# mic.net
KiCad netlist of a schematic drawn in Altium Designer
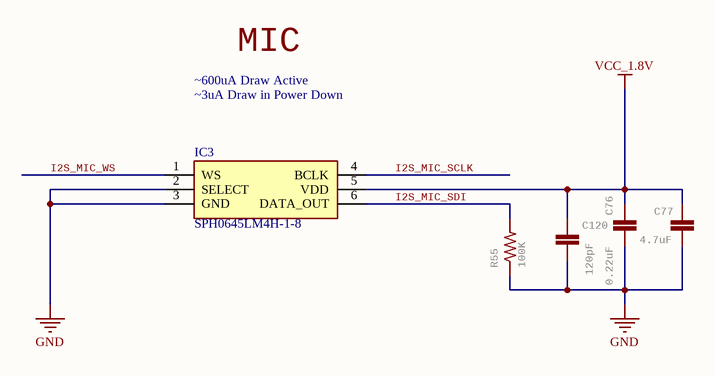
[diagram p0: mic.SchDoc]

(export (version "E")
  (design (tool "Eeschema 10.0.6"))
  (components
    (comp (ref "C76")
      (value "0.22uF")
      (footprint "C0201")
      (description "CAPACITOR, European symbol")
      (fields (field (name "MPN") "GRM033R60J224ME15D"))
      (libsource (lib "openmv-ae3") (part "C-EUC0201"))
    )
    (comp (ref "C77")
      (value "4.7uF")
      (footprint "0402-CAP")
      (description "CapacitorStandard 0603 ceramic capacitor, and 0.1\" leaded capacitor.")
      (fields (field (name "MPN") "JMK105BBJ475MV-F") (field (name "LIBRARYNAME") "sfe"))
      (libsource (lib "openmv-ae3") (part "CAP0402-CAP"))
    )
    (comp (ref "C120")
      (value "120pF")
      (footprint "C0201")
      (fields (field (name "MPN") "GRM033R71H121KA12D") (field (name "LIBRARYNAME") "sfe"))
      (libsource (lib "openmv-ae3") (part "CAP0402-CAP"))
    )
    (comp (ref "IC3")
      (value "SPH0645LM4H-1-8")
      (footprint "SamacSys:SPH0645LM4H18")
      (description "Integrated Circuit")
      (fields (field (name "MOUSER PART NUMBER") "721-SPH0645LM4H-1-8"))
      (libsource (lib "openmv-ae3") (part "SPH0645LM4H-1-8"))
    )
    (comp (ref "R55")
      (value "100K")
      (footprint "R0201")
      (fields (field (name "MPN") "RMCF0201FT100K") (field (name "LIBRARYNAME") "sfe"))
      (libsource (lib "openmv-ae3") (part "RESISTOR0402-RES"))
    )
  )
  (nets
    (net (code "1") (name "/I2S_MIC_SCLK") (class "Default")
      (node (ref "IC3") (pin "4") (pinfunction "BCLK_4") (pintype "passive"))
    )
    (net (code "2") (name "/I2S_MIC_SDI") (class "Default")
      (node (ref "IC3") (pin "6") (pinfunction "DATA_OUT_6") (pintype "passive"))
      (node (ref "R55") (pin "2") (pinfunction "2_2") (pintype "passive"))
    )
    (net (code "3") (name "/I2S_MIC_WS") (class "Default")
      (node (ref "IC3") (pin "1") (pinfunction "WS_1") (pintype "passive"))
    )
    (net (code "4") (name "GND") (class "Default")
      (node (ref "C120") (pin "1") (pinfunction "1_1") (pintype "passive"))
      (node (ref "C76") (pin "2") (pinfunction "2_2") (pintype "passive"))
      (node (ref "C77") (pin "1") (pinfunction "1_1") (pintype "passive"))
      (node (ref "IC3") (pin "2") (pinfunction "SELECT_2") (pintype "passive"))
      (node (ref "IC3") (pin "3") (pinfunction "GND_3") (pintype "passive"))
      (node (ref "R55") (pin "1") (pinfunction "1_1") (pintype "passive"))
    )
    (net (code "5") (name "VCC_1.8V") (class "Default")
      (node (ref "C120") (pin "2") (pinfunction "2_2") (pintype "passive"))
      (node (ref "C76") (pin "1") (pinfunction "1_1") (pintype "passive"))
      (node (ref "C77") (pin "2") (pinfunction "2_2") (pintype "passive"))
      (node (ref "IC3") (pin "5") (pinfunction "VDD_5") (pintype "passive"))
    )
  )
)
